# TM4C-Interfaces.net
KiCad netlist of a schematic drawn in Altium Designer
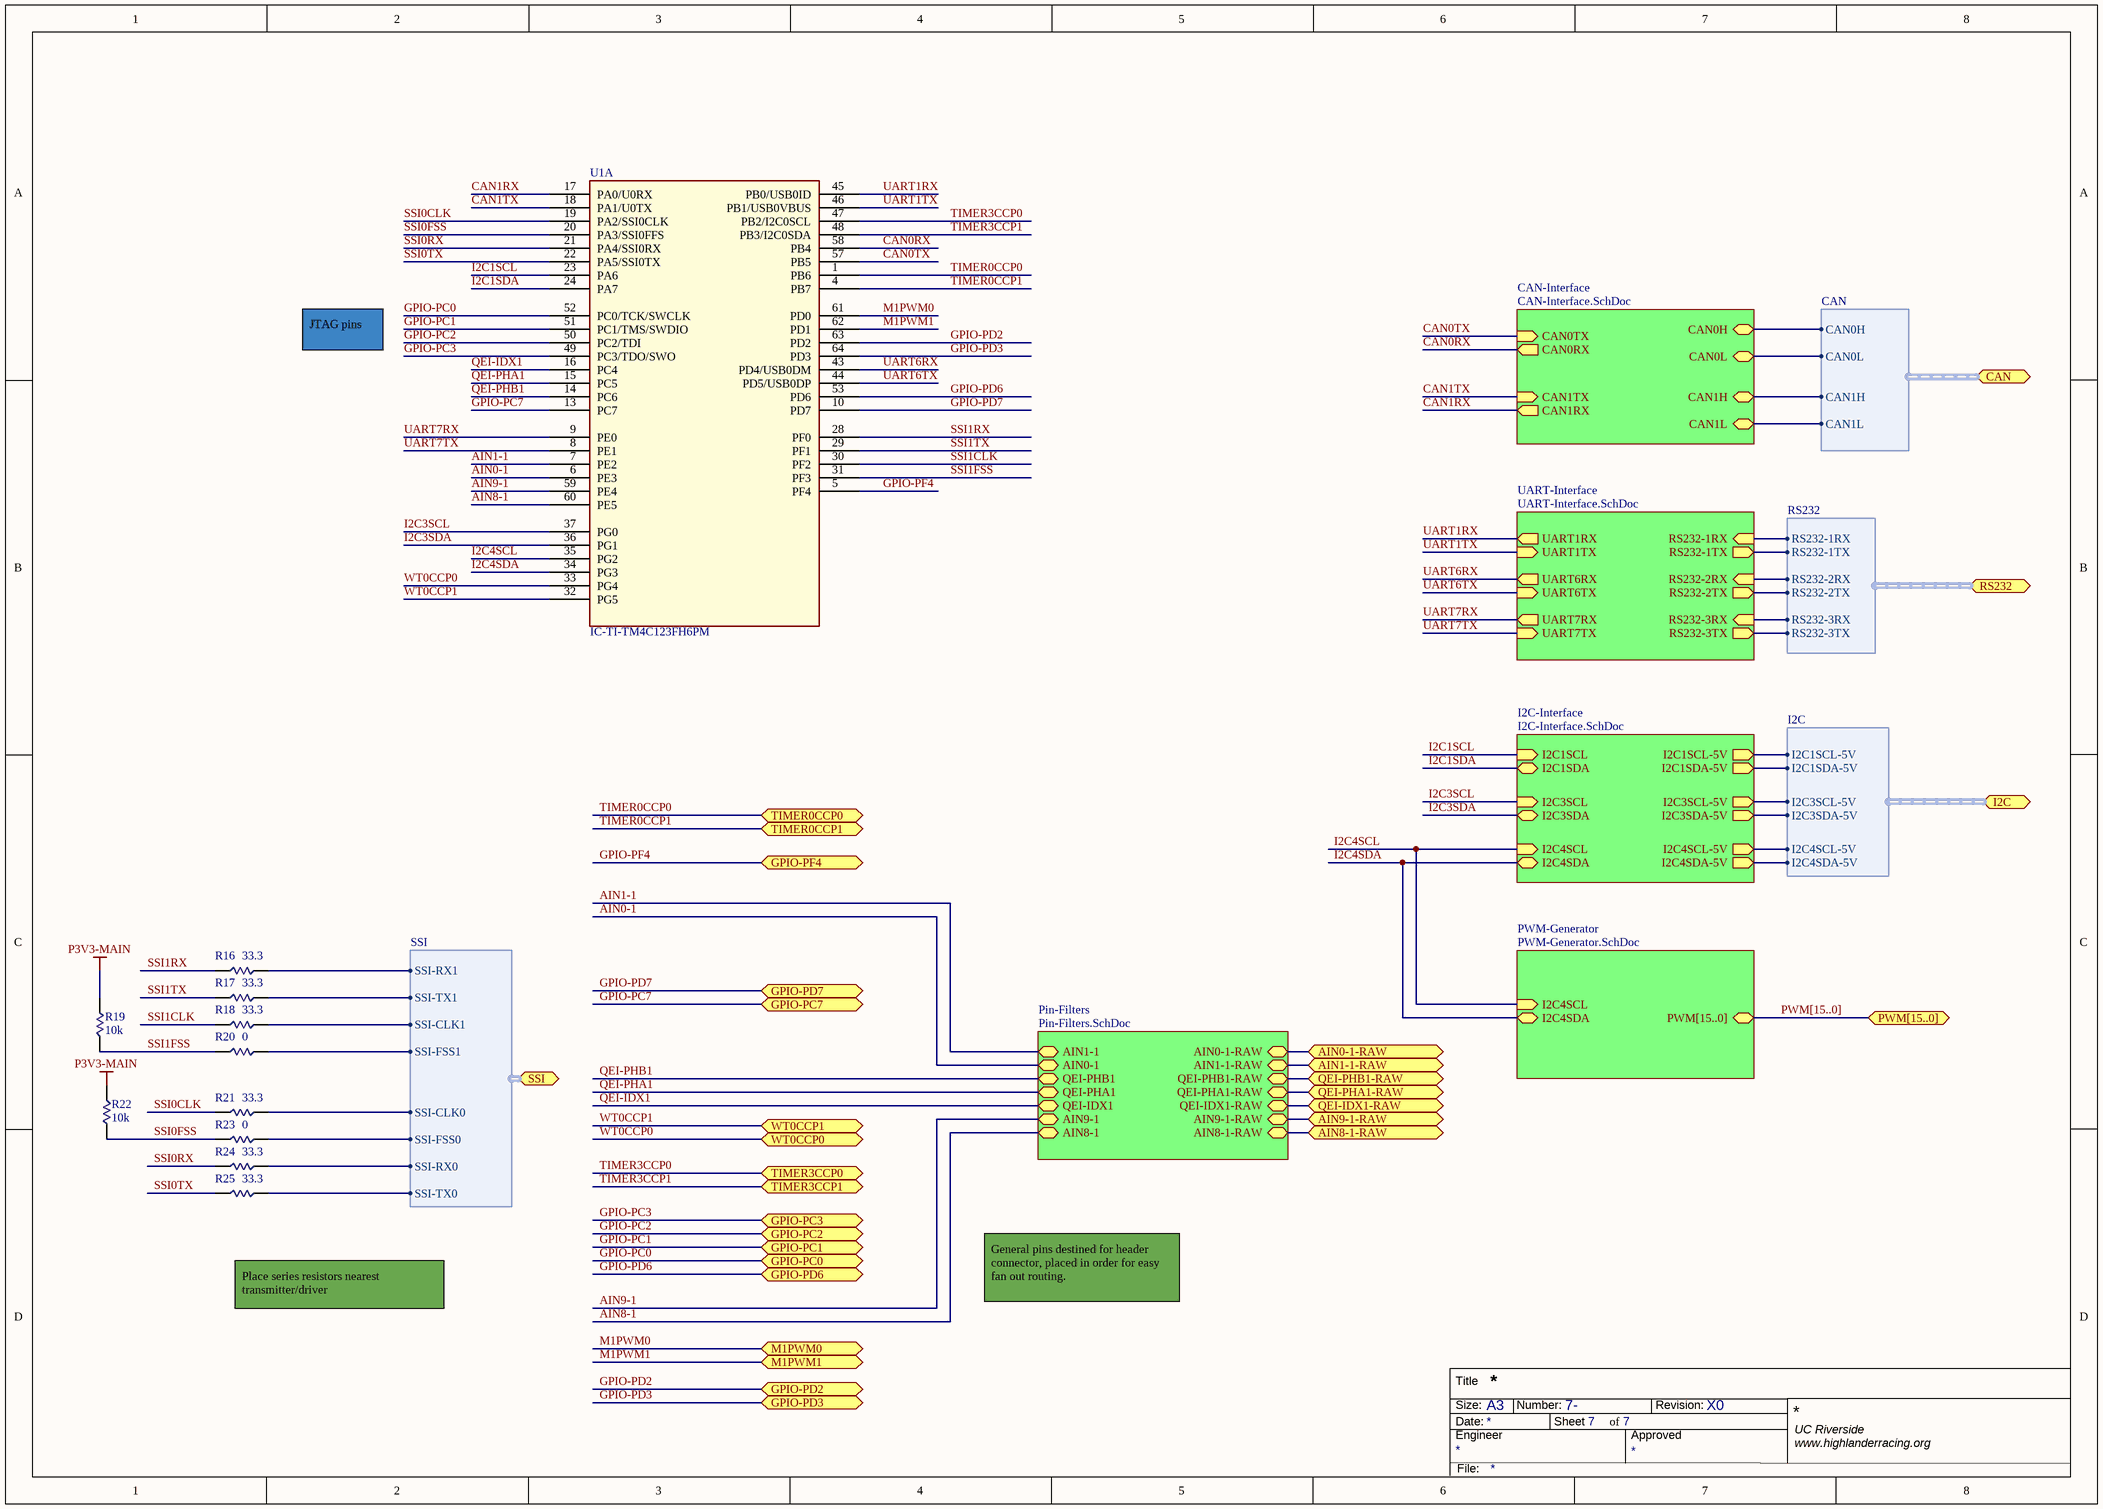
[diagram p0: TM4C-Interfaces.SchDoc]

(export (version "E")
  (design (tool "Eeschema 10.0.6"))
  (components
    (comp (ref "R16")
      (value "33.3")
      (footprint "FOOTPRINT-0805-GEN")
      (description "1/8 Watt Surface Mount Resistor")
      (fields (field (name "Comment") "SMC"))
      (libsource (lib "HR-Master-Integrated") (part "Resistor-Generic-0805-2012"))
    )
    (comp (ref "R17")
      (value "33.3")
      (footprint "FOOTPRINT-0805-GEN")
      (description "1/8 Watt Surface Mount Resistor")
      (fields (field (name "Comment") "SMC"))
      (libsource (lib "HR-Master-Integrated") (part "Resistor-Generic-0805-2012"))
    )
    (comp (ref "R18")
      (value "33.3")
      (footprint "FOOTPRINT-0805-GEN")
      (description "1/8 Watt Surface Mount Resistor")
      (fields (field (name "Comment") "SMC"))
      (libsource (lib "HR-Master-Integrated") (part "Resistor-Generic-0805-2012"))
    )
    (comp (ref "R19")
      (value "10k")
      (footprint "FOOTPRINT-0805-GEN")
      (description "1/8 Watt Surface Mount Resistor")
      (fields (field (name "Comment") "SMC"))
      (libsource (lib "HR-Master-Integrated") (part "Resistor-Generic-0805-2012"))
    )
    (comp (ref "R20")
      (value "0")
      (footprint "FOOTPRINT-0805-GEN")
      (description "1/8 Watt Surface Mount Resistor")
      (fields (field (name "Comment") "SMC"))
      (libsource (lib "HR-Master-Integrated") (part "Resistor-Generic-0805-2012"))
    )
    (comp (ref "R21")
      (value "33.3")
      (footprint "FOOTPRINT-0805-GEN")
      (description "1/8 Watt Surface Mount Resistor")
      (fields (field (name "Comment") "SMC"))
      (libsource (lib "HR-Master-Integrated") (part "Resistor-Generic-0805-2012"))
    )
    (comp (ref "R22")
      (value "10k")
      (footprint "FOOTPRINT-0805-GEN")
      (description "1/8 Watt Surface Mount Resistor")
      (fields (field (name "Comment") "SMC"))
      (libsource (lib "HR-Master-Integrated") (part "Resistor-Generic-0805-2012"))
    )
    (comp (ref "R23")
      (value "0")
      (footprint "FOOTPRINT-0805-GEN")
      (description "1/8 Watt Surface Mount Resistor")
      (fields (field (name "Comment") "SMC"))
      (libsource (lib "HR-Master-Integrated") (part "Resistor-Generic-0805-2012"))
    )
    (comp (ref "R24")
      (value "33.3")
      (footprint "FOOTPRINT-0805-GEN")
      (description "1/8 Watt Surface Mount Resistor")
      (fields (field (name "Comment") "SMC"))
      (libsource (lib "HR-Master-Integrated") (part "Resistor-Generic-0805-2012"))
    )
    (comp (ref "R25")
      (value "33.3")
      (footprint "FOOTPRINT-0805-GEN")
      (description "1/8 Watt Surface Mount Resistor")
      (fields (field (name "Comment") "SMC"))
      (libsource (lib "HR-Master-Integrated") (part "Resistor-Generic-0805-2012"))
    )
    (comp (ref "U1")
      (value "IC-TI-TM4C123FH6PM")
      (footprint "FOOTPRINT-TI-TM4C123-64-LQFP")
      (libsource (lib "HR-Master-Integrated") (part "IC-TI-TM4C123FH6PM"))
    )
  )
  (nets
    (net (code "21") (name "/AIN0-1") (class "Default")
      (node (ref "U1") (pin "6") (pinfunction "PE3_6") (pintype "passive"))
    )
    (net (code "23") (name "/AIN1-1") (class "Default")
      (node (ref "U1") (pin "7") (pinfunction "PE2_7") (pintype "passive"))
    )
    (net (code "25") (name "/AIN8-1") (class "Default")
      (node (ref "U1") (pin "60") (pinfunction "PE5_60") (pintype "passive"))
    )
    (net (code "27") (name "/AIN9-1") (class "Default")
      (node (ref "U1") (pin "59") (pinfunction "PE4_59") (pintype "passive"))
    )
    (net (code "31") (name "/CAN0RX") (class "Default")
      (node (ref "U1") (pin "58") (pinfunction "PB4_58") (pintype "passive"))
    )
    (net (code "32") (name "/CAN0TX") (class "Default")
      (node (ref "U1") (pin "57") (pinfunction "PB5_57") (pintype "passive"))
    )
    (net (code "35") (name "/CAN1RX") (class "Default")
      (node (ref "U1") (pin "17") (pinfunction "PA0/U0RX_17") (pintype "passive"))
    )
    (net (code "36") (name "/CAN1TX") (class "Default")
      (node (ref "U1") (pin "18") (pinfunction "PA1/U0TX_18") (pintype "passive"))
    )
    (net (code "37") (name "/GPIO-PC0") (class "Default")
      (node (ref "U1") (pin "52") (pinfunction "PC0/TCK/SWCLK_52") (pintype "passive"))
    )
    (net (code "38") (name "/GPIO-PC1") (class "Default")
      (node (ref "U1") (pin "51") (pinfunction "PC1/TMS/SWDIO_51") (pintype "passive"))
    )
    (net (code "39") (name "/GPIO-PC2") (class "Default")
      (node (ref "U1") (pin "50") (pinfunction "PC2/TDI_50") (pintype "passive"))
    )
    (net (code "40") (name "/GPIO-PC3") (class "Default")
      (node (ref "U1") (pin "49") (pinfunction "PC3/TDO/SWO_49") (pintype "passive"))
    )
    (net (code "41") (name "/GPIO-PC7") (class "Default")
      (node (ref "U1") (pin "13") (pinfunction "PC7_13") (pintype "passive"))
    )
    (net (code "42") (name "/GPIO-PD2") (class "Default")
      (node (ref "U1") (pin "63") (pinfunction "PD2_63") (pintype "passive"))
    )
    (net (code "43") (name "/GPIO-PD3") (class "Default")
      (node (ref "U1") (pin "64") (pinfunction "PD3_64") (pintype "passive"))
    )
    (net (code "44") (name "/GPIO-PD6") (class "Default")
      (node (ref "U1") (pin "53") (pinfunction "PD6_53") (pintype "passive"))
    )
    (net (code "45") (name "/GPIO-PD7") (class "Default")
      (node (ref "U1") (pin "10") (pinfunction "PD7_10") (pintype "passive"))
    )
    (net (code "46") (name "/GPIO-PF4") (class "Default")
      (node (ref "U1") (pin "5") (pinfunction "PF4_5") (pintype "passive"))
    )
    (net (code "47") (name "/I2C1SCL") (class "Default")
      (node (ref "U1") (pin "23") (pinfunction "PA6_23") (pintype "passive"))
    )
    (net (code "49") (name "/I2C1SDA") (class "Default")
      (node (ref "U1") (pin "24") (pinfunction "PA7_24") (pintype "passive"))
    )
    (net (code "51") (name "/I2C3SCL") (class "Default")
      (node (ref "U1") (pin "37") (pinfunction "PG0_37") (pintype "passive"))
    )
    (net (code "53") (name "/I2C3SDA") (class "Default")
      (node (ref "U1") (pin "36") (pinfunction "PG1_36") (pintype "passive"))
    )
    (net (code "55") (name "/I2C4SCL") (class "Default")
      (node (ref "U1") (pin "35") (pinfunction "PG2_35") (pintype "passive"))
    )
    (net (code "57") (name "/I2C4SDA") (class "Default")
      (node (ref "U1") (pin "34") (pinfunction "PG3_34") (pintype "passive"))
    )
    (net (code "59") (name "/M1PWM0") (class "Default")
      (node (ref "U1") (pin "61") (pinfunction "PD0_61") (pintype "passive"))
    )
    (net (code "60") (name "/M1PWM1") (class "Default")
      (node (ref "U1") (pin "62") (pinfunction "PD1_62") (pintype "passive"))
    )
    (net (code "62") (name "/QEI-IDX1") (class "Default")
      (node (ref "U1") (pin "16") (pinfunction "PC4_16") (pintype "passive"))
    )
    (net (code "64") (name "/QEI-PHA1") (class "Default")
      (node (ref "U1") (pin "15") (pinfunction "PC5_15") (pintype "passive"))
    )
    (net (code "66") (name "/QEI-PHB1") (class "Default")
      (node (ref "U1") (pin "14") (pinfunction "PC6_14") (pintype "passive"))
    )
    (net (code "74") (name "/SSI-CLK0") (class "Default")
      (node (ref "R21") (pin "2") (pinfunction "2_2") (pintype "passive"))
    )
    (net (code "75") (name "/SSI-CLK1") (class "Default")
      (node (ref "R18") (pin "2") (pinfunction "2_2") (pintype "passive"))
    )
    (net (code "76") (name "/SSI-FSS0") (class "Default")
      (node (ref "R23") (pin "2") (pinfunction "2_2") (pintype "passive"))
    )
    (net (code "77") (name "/SSI-FSS1") (class "Default")
      (node (ref "R20") (pin "2") (pinfunction "2_2") (pintype "passive"))
    )
    (net (code "78") (name "/SSI-RX0") (class "Default")
      (node (ref "R24") (pin "2") (pinfunction "2_2") (pintype "passive"))
    )
    (net (code "79") (name "/SSI-RX1") (class "Default")
      (node (ref "R16") (pin "2") (pinfunction "2_2") (pintype "passive"))
    )
    (net (code "80") (name "/SSI-TX0") (class "Default")
      (node (ref "R25") (pin "2") (pinfunction "2_2") (pintype "passive"))
    )
    (net (code "81") (name "/SSI-TX1") (class "Default")
      (node (ref "R17") (pin "2") (pinfunction "2_2") (pintype "passive"))
    )
    (net (code "82") (name "/SSI0CLK") (class "Default")
      (node (ref "R21") (pin "1") (pinfunction "1_1") (pintype "passive"))
      (node (ref "U1") (pin "19") (pinfunction "PA2/SSI0CLK_19") (pintype "passive"))
    )
    (net (code "83") (name "/SSI0FSS") (class "Default")
      (node (ref "R22") (pin "1") (pinfunction "1_1") (pintype "passive"))
      (node (ref "R23") (pin "1") (pinfunction "1_1") (pintype "passive"))
      (node (ref "U1") (pin "20") (pinfunction "PA3/SSI0FFS_20") (pintype "passive"))
    )
    (net (code "84") (name "/SSI0RX") (class "Default")
      (node (ref "R24") (pin "1") (pinfunction "1_1") (pintype "passive"))
      (node (ref "U1") (pin "21") (pinfunction "PA4/SSI0RX_21") (pintype "passive"))
    )
    (net (code "85") (name "/SSI0TX") (class "Default")
      (node (ref "R25") (pin "1") (pinfunction "1_1") (pintype "passive"))
      (node (ref "U1") (pin "22") (pinfunction "PA5/SSI0TX_22") (pintype "passive"))
    )
    (net (code "86") (name "/SSI1CLK") (class "Default")
      (node (ref "R18") (pin "1") (pinfunction "1_1") (pintype "passive"))
      (node (ref "U1") (pin "30") (pinfunction "PF2_30") (pintype "passive"))
    )
    (net (code "87") (name "/SSI1FSS") (class "Default")
      (node (ref "R19") (pin "1") (pinfunction "1_1") (pintype "passive"))
      (node (ref "R20") (pin "1") (pinfunction "1_1") (pintype "passive"))
      (node (ref "U1") (pin "31") (pinfunction "PF3_31") (pintype "passive"))
    )
    (net (code "88") (name "/SSI1RX") (class "Default")
      (node (ref "R16") (pin "1") (pinfunction "1_1") (pintype "passive"))
      (node (ref "U1") (pin "28") (pinfunction "PF0_28") (pintype "passive"))
    )
    (net (code "89") (name "/SSI1TX") (class "Default")
      (node (ref "R17") (pin "1") (pinfunction "1_1") (pintype "passive"))
      (node (ref "U1") (pin "29") (pinfunction "PF1_29") (pintype "passive"))
    )
    (net (code "90") (name "/TIMER0CCP0") (class "Default")
      (node (ref "U1") (pin "1") (pinfunction "PB6_1") (pintype "passive"))
    )
    (net (code "91") (name "/TIMER0CCP1") (class "Default")
      (node (ref "U1") (pin "4") (pinfunction "PB7_4") (pintype "passive"))
    )
    (net (code "92") (name "/TIMER3CCP0") (class "Default")
      (node (ref "U1") (pin "47") (pinfunction "PB2/I2C0SCL_47") (pintype "passive"))
    )
    (net (code "93") (name "/TIMER3CCP1") (class "Default")
      (node (ref "U1") (pin "48") (pinfunction "PB3/I2C0SDA_48") (pintype "passive"))
    )
    (net (code "94") (name "/UART1RX") (class "Default")
      (node (ref "U1") (pin "45") (pinfunction "PB0/USB0ID_45") (pintype "passive"))
    )
    (net (code "95") (name "/UART1TX") (class "Default")
      (node (ref "U1") (pin "46") (pinfunction "PB1/USB0VBUS_46") (pintype "passive"))
    )
    (net (code "96") (name "/UART6RX") (class "Default")
      (node (ref "U1") (pin "43") (pinfunction "PD4/USB0DM_43") (pintype "passive"))
    )
    (net (code "97") (name "/UART6TX") (class "Default")
      (node (ref "U1") (pin "44") (pinfunction "PD5/USB0DP_44") (pintype "passive"))
    )
    (net (code "98") (name "/UART7RX") (class "Default")
      (node (ref "U1") (pin "9") (pinfunction "PE0_9") (pintype "passive"))
    )
    (net (code "99") (name "/UART7TX") (class "Default")
      (node (ref "U1") (pin "8") (pinfunction "PE1_8") (pintype "passive"))
    )
    (net (code "100") (name "/WT0CCP0") (class "Default")
      (node (ref "U1") (pin "33") (pinfunction "PG4_33") (pintype "passive"))
    )
    (net (code "101") (name "/WT0CCP1") (class "Default")
      (node (ref "U1") (pin "32") (pinfunction "PG5_32") (pintype "passive"))
    )
    (net (code "106") (name "P3V3-MAIN") (class "Default")
      (node (ref "R19") (pin "2") (pinfunction "2_2") (pintype "passive"))
      (node (ref "R22") (pin "2") (pinfunction "2_2") (pintype "passive"))
    )
  )
)
